# servos.net
KiCad netlist of a schematic drawn in Altium Designer
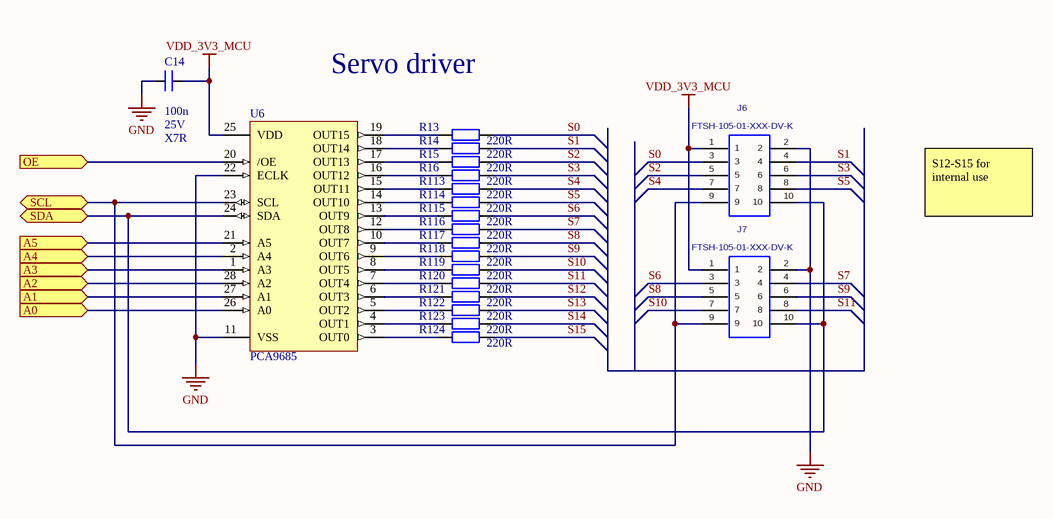
[diagram p0: servos.SchDoc]

(export (version "E")
  (design (tool "Eeschema 10.0.6"))
  (components
    (comp (ref "C14")
      (value "100n")
      (footprint "C1005[0402]")
      (description "Capacitor")
      (fields (field (name "VOLTAGE") "25V") (field (name "TYPE") "X7R") (field (name "Comment") "cap"))
      (libsource (lib "gpa_passives") (part "cap"))
    )
    (comp (ref "J6")
      (value "FTSH-105-01-XXX-DV-K")
      (footprint "FTSH-105-01-XXX-DV-K")
      (description "TERMINAL STRIP, .050\"(1.27mm) PITCH, 10 PINS, KEYED")
      (fields (field (name "MANUFACTURER") "SAMTEC") (field (name "CREATED") "November 30, 2016 - Wendy Xin"))
      (libsource (lib "FTSH-105-01-XXX-DV-K") (part "FTSH-105-01-XXX-DV-K"))
    )
    (comp (ref "J7")
      (value "FTSH-105-01-XXX-DV-K")
      (footprint "FTSH-105-01-XXX-DV-K")
      (description "TERMINAL STRIP, .050\"(1.27mm) PITCH, 10 PINS, KEYED")
      (fields (field (name "MANUFACTURER") "SAMTEC") (field (name "CREATED") "November 30, 2016 - Wendy Xin"))
      (libsource (lib "FTSH-105-01-XXX-DV-K") (part "FTSH-105-01-XXX-DV-K"))
    )
    (comp (ref "R13")
      (value "220R")
      (footprint "R1005[0402]")
      (description "Resistor")
      (fields (field (name "TOLERANCE") "5%") (field (name "Comment") "res"))
      (libsource (lib "gpa_passives") (part "res"))
    )
    (comp (ref "R14")
      (value "220R")
      (footprint "R1005[0402]")
      (description "Resistor")
      (fields (field (name "TOLERANCE") "5%") (field (name "Comment") "res"))
      (libsource (lib "gpa_passives") (part "res"))
    )
    (comp (ref "R15")
      (value "220R")
      (footprint "R1005[0402]")
      (description "Resistor")
      (fields (field (name "TOLERANCE") "5%") (field (name "Comment") "res"))
      (libsource (lib "gpa_passives") (part "res"))
    )
    (comp (ref "R16")
      (value "220R")
      (footprint "R1005[0402]")
      (description "Resistor")
      (fields (field (name "TOLERANCE") "5%") (field (name "Comment") "res"))
      (libsource (lib "gpa_passives") (part "res"))
    )
    (comp (ref "R113")
      (value "220R")
      (footprint "R1005[0402]")
      (description "Resistor")
      (fields (field (name "TOLERANCE") "5%") (field (name "Comment") "res"))
      (libsource (lib "gpa_passives") (part "res"))
    )
    (comp (ref "R114")
      (value "220R")
      (footprint "R1005[0402]")
      (description "Resistor")
      (fields (field (name "TOLERANCE") "5%") (field (name "Comment") "res"))
      (libsource (lib "gpa_passives") (part "res"))
    )
    (comp (ref "R115")
      (value "220R")
      (footprint "R1005[0402]")
      (description "Resistor")
      (fields (field (name "TOLERANCE") "5%") (field (name "Comment") "res"))
      (libsource (lib "gpa_passives") (part "res"))
    )
    (comp (ref "R116")
      (value "220R")
      (footprint "R1005[0402]")
      (description "Resistor")
      (fields (field (name "TOLERANCE") "5%") (field (name "Comment") "res"))
      (libsource (lib "gpa_passives") (part "res"))
    )
    (comp (ref "R117")
      (value "220R")
      (footprint "R1005[0402]")
      (description "Resistor")
      (fields (field (name "TOLERANCE") "5%") (field (name "Comment") "res"))
      (libsource (lib "gpa_passives") (part "res"))
    )
    (comp (ref "R118")
      (value "220R")
      (footprint "R1005[0402]")
      (description "Resistor")
      (fields (field (name "TOLERANCE") "5%") (field (name "Comment") "res"))
      (libsource (lib "gpa_passives") (part "res"))
    )
    (comp (ref "R119")
      (value "220R")
      (footprint "R1005[0402]")
      (description "Resistor")
      (fields (field (name "TOLERANCE") "5%") (field (name "Comment") "res"))
      (libsource (lib "gpa_passives") (part "res"))
    )
    (comp (ref "R120")
      (value "220R")
      (footprint "R1005[0402]")
      (description "Resistor")
      (fields (field (name "TOLERANCE") "5%") (field (name "Comment") "res"))
      (libsource (lib "gpa_passives") (part "res"))
    )
    (comp (ref "R121")
      (value "220R")
      (footprint "R1005[0402]")
      (description "Resistor")
      (fields (field (name "TOLERANCE") "5%") (field (name "Comment") "res"))
      (libsource (lib "gpa_passives") (part "res"))
    )
    (comp (ref "R122")
      (value "220R")
      (footprint "R1005[0402]")
      (description "Resistor")
      (fields (field (name "TOLERANCE") "5%") (field (name "Comment") "res"))
      (libsource (lib "gpa_passives") (part "res"))
    )
    (comp (ref "R123")
      (value "220R")
      (footprint "R1005[0402]")
      (description "Resistor")
      (fields (field (name "TOLERANCE") "5%") (field (name "Comment") "res"))
      (libsource (lib "gpa_passives") (part "res"))
    )
    (comp (ref "R124")
      (value "220R")
      (footprint "R1005[0402]")
      (description "Resistor")
      (fields (field (name "TOLERANCE") "5%") (field (name "Comment") "res"))
      (libsource (lib "gpa_passives") (part "res"))
    )
    (comp (ref "U6")
      (value "PCA9685")
      (footprint "NXP_QFN65P600X600X100_HS-29M")
      (libsource (lib "gpa_nxp") (part "pca9685"))
    )
  )
  (nets
    (net (code "1") (name "/A0") (class "Default")
      (node (ref "U6") (pin "26") (pinfunction "A0_26") (pintype "input"))
    )
    (net (code "2") (name "/A1") (class "Default")
      (node (ref "U6") (pin "27") (pinfunction "A1_27") (pintype "input"))
    )
    (net (code "3") (name "/A2") (class "Default")
      (node (ref "U6") (pin "28") (pinfunction "A2_28") (pintype "input"))
    )
    (net (code "4") (name "/A3") (class "Default")
      (node (ref "U6") (pin "1") (pinfunction "A3_1") (pintype "input"))
    )
    (net (code "5") (name "/A4") (class "Default")
      (node (ref "U6") (pin "2") (pinfunction "A4_2") (pintype "input"))
    )
    (net (code "6") (name "/A5") (class "Default")
      (node (ref "U6") (pin "21") (pinfunction "A5_21") (pintype "input"))
    )
    (net (code "7") (name "/OE") (class "Default")
      (node (ref "U6") (pin "20") (pinfunction "/OE_20") (pintype "input"))
    )
    (net (code "8") (name "/S0") (class "Default")
      (node (ref "J6") (pin "3") (pinfunction "3_3") (pintype "passive"))
      (node (ref "R13") (pin "2") (pinfunction "2_2") (pintype "passive"))
    )
    (net (code "9") (name "/S1") (class "Default")
      (node (ref "J6") (pin "4") (pinfunction "4_4") (pintype "passive"))
      (node (ref "R14") (pin "2") (pinfunction "2_2") (pintype "passive"))
    )
    (net (code "10") (name "/S2") (class "Default")
      (node (ref "J6") (pin "5") (pinfunction "5_5") (pintype "passive"))
      (node (ref "R15") (pin "2") (pinfunction "2_2") (pintype "passive"))
    )
    (net (code "11") (name "/S3") (class "Default")
      (node (ref "J6") (pin "6") (pinfunction "6_6") (pintype "passive"))
      (node (ref "R16") (pin "2") (pinfunction "2_2") (pintype "passive"))
    )
    (net (code "12") (name "/S4") (class "Default")
      (node (ref "J6") (pin "7") (pinfunction "7_7") (pintype "passive"))
      (node (ref "R113") (pin "2") (pinfunction "2_2") (pintype "passive"))
    )
    (net (code "13") (name "/S5") (class "Default")
      (node (ref "J6") (pin "8") (pinfunction "8_8") (pintype "passive"))
      (node (ref "R114") (pin "2") (pinfunction "2_2") (pintype "passive"))
    )
    (net (code "14") (name "/S6") (class "Default")
      (node (ref "J7") (pin "3") (pinfunction "3_3") (pintype "passive"))
      (node (ref "R115") (pin "2") (pinfunction "2_2") (pintype "passive"))
    )
    (net (code "15") (name "/S7") (class "Default")
      (node (ref "J7") (pin "4") (pinfunction "4_4") (pintype "passive"))
      (node (ref "R116") (pin "2") (pinfunction "2_2") (pintype "passive"))
    )
    (net (code "16") (name "/S8") (class "Default")
      (node (ref "J7") (pin "5") (pinfunction "5_5") (pintype "passive"))
      (node (ref "R117") (pin "2") (pinfunction "2_2") (pintype "passive"))
    )
    (net (code "17") (name "/S9") (class "Default")
      (node (ref "J7") (pin "6") (pinfunction "6_6") (pintype "passive"))
      (node (ref "R118") (pin "2") (pinfunction "2_2") (pintype "passive"))
    )
    (net (code "18") (name "/S10") (class "Default")
      (node (ref "J7") (pin "7") (pinfunction "7_7") (pintype "passive"))
      (node (ref "R119") (pin "2") (pinfunction "2_2") (pintype "passive"))
    )
    (net (code "19") (name "/S11") (class "Default")
      (node (ref "J7") (pin "8") (pinfunction "8_8") (pintype "passive"))
      (node (ref "R120") (pin "2") (pinfunction "2_2") (pintype "passive"))
    )
    (net (code "20") (name "/S12") (class "Default")
      (node (ref "R121") (pin "2") (pinfunction "2_2") (pintype "passive"))
    )
    (net (code "21") (name "/S13") (class "Default")
      (node (ref "R122") (pin "2") (pinfunction "2_2") (pintype "passive"))
    )
    (net (code "22") (name "/S14") (class "Default")
      (node (ref "R123") (pin "2") (pinfunction "2_2") (pintype "passive"))
    )
    (net (code "23") (name "/S15") (class "Default")
      (node (ref "R124") (pin "2") (pinfunction "2_2") (pintype "passive"))
    )
    (net (code "24") (name "/SCL") (class "Default")
      (node (ref "J6") (pin "9") (pinfunction "9_9") (pintype "passive"))
      (node (ref "J7") (pin "9") (pinfunction "9_9") (pintype "passive"))
      (node (ref "U6") (pin "23") (pinfunction "SCL_23") (pintype "bidirectional"))
    )
    (net (code "25") (name "/SDA") (class "Default")
      (node (ref "J6") (pin "10") (pinfunction "10_10") (pintype "passive"))
      (node (ref "J7") (pin "10") (pinfunction "10_10") (pintype "passive"))
      (node (ref "U6") (pin "24") (pinfunction "SDA_24") (pintype "bidirectional"))
    )
    (net (code "26") (name "GND") (class "Default")
      (node (ref "C14") (pin "1") (pinfunction "1_1") (pintype "passive"))
      (node (ref "J6") (pin "2") (pinfunction "2_2") (pintype "passive"))
      (node (ref "J7") (pin "2") (pinfunction "2_2") (pintype "passive"))
      (node (ref "U6") (pin "11") (pinfunction "VSS_11") (pintype "power_in"))
      (node (ref "U6") (pin "22") (pinfunction "ECLK_22") (pintype "input"))
    )
    (net (code "27") (name "Net-(U6-OUT0)") (class "Default")
      (node (ref "R124") (pin "1") (pinfunction "1_1") (pintype "passive"))
      (node (ref "U6") (pin "3") (pinfunction "OUT0_3") (pintype "output"))
    )
    (net (code "28") (name "Net-(U6-OUT1)") (class "Default")
      (node (ref "R123") (pin "1") (pinfunction "1_1") (pintype "passive"))
      (node (ref "U6") (pin "4") (pinfunction "OUT1_4") (pintype "output"))
    )
    (net (code "29") (name "Net-(U6-OUT2)") (class "Default")
      (node (ref "R122") (pin "1") (pinfunction "1_1") (pintype "passive"))
      (node (ref "U6") (pin "5") (pinfunction "OUT2_5") (pintype "output"))
    )
    (net (code "30") (name "Net-(U6-OUT3)") (class "Default")
      (node (ref "R121") (pin "1") (pinfunction "1_1") (pintype "passive"))
      (node (ref "U6") (pin "6") (pinfunction "OUT3_6") (pintype "output"))
    )
    (net (code "31") (name "Net-(U6-OUT4)") (class "Default")
      (node (ref "R120") (pin "1") (pinfunction "1_1") (pintype "passive"))
      (node (ref "U6") (pin "7") (pinfunction "OUT4_7") (pintype "output"))
    )
    (net (code "32") (name "Net-(U6-OUT5)") (class "Default")
      (node (ref "R119") (pin "1") (pinfunction "1_1") (pintype "passive"))
      (node (ref "U6") (pin "8") (pinfunction "OUT5_8") (pintype "output"))
    )
    (net (code "33") (name "Net-(U6-OUT6)") (class "Default")
      (node (ref "R118") (pin "1") (pinfunction "1_1") (pintype "passive"))
      (node (ref "U6") (pin "9") (pinfunction "OUT6_9") (pintype "output"))
    )
    (net (code "34") (name "Net-(U6-OUT7)") (class "Default")
      (node (ref "R117") (pin "1") (pinfunction "1_1") (pintype "passive"))
      (node (ref "U6") (pin "10") (pinfunction "OUT7_10") (pintype "output"))
    )
    (net (code "35") (name "Net-(U6-OUT8)") (class "Default")
      (node (ref "R116") (pin "1") (pinfunction "1_1") (pintype "passive"))
      (node (ref "U6") (pin "12") (pinfunction "OUT8_12") (pintype "output"))
    )
    (net (code "36") (name "Net-(U6-OUT9)") (class "Default")
      (node (ref "R115") (pin "1") (pinfunction "1_1") (pintype "passive"))
      (node (ref "U6") (pin "13") (pinfunction "OUT9_13") (pintype "output"))
    )
    (net (code "37") (name "Net-(U6-OUT10)") (class "Default")
      (node (ref "R114") (pin "1") (pinfunction "1_1") (pintype "passive"))
      (node (ref "U6") (pin "14") (pinfunction "OUT10_14") (pintype "output"))
    )
    (net (code "38") (name "Net-(U6-OUT11)") (class "Default")
      (node (ref "R113") (pin "1") (pinfunction "1_1") (pintype "passive"))
      (node (ref "U6") (pin "15") (pinfunction "OUT11_15") (pintype "output"))
    )
    (net (code "39") (name "Net-(U6-OUT12)") (class "Default")
      (node (ref "R16") (pin "1") (pinfunction "1_1") (pintype "passive"))
      (node (ref "U6") (pin "16") (pinfunction "OUT12_16") (pintype "output"))
    )
    (net (code "40") (name "Net-(U6-OUT13)") (class "Default")
      (node (ref "R15") (pin "1") (pinfunction "1_1") (pintype "passive"))
      (node (ref "U6") (pin "17") (pinfunction "OUT13_17") (pintype "output"))
    )
    (net (code "41") (name "Net-(U6-OUT14)") (class "Default")
      (node (ref "R14") (pin "1") (pinfunction "1_1") (pintype "passive"))
      (node (ref "U6") (pin "18") (pinfunction "OUT14_18") (pintype "output"))
    )
    (net (code "42") (name "Net-(U6-OUT15)") (class "Default")
      (node (ref "R13") (pin "1") (pinfunction "1_1") (pintype "passive"))
      (node (ref "U6") (pin "19") (pinfunction "OUT15_19") (pintype "output"))
    )
    (net (code "43") (name "VDD_3V3_MCU") (class "Default")
      (node (ref "C14") (pin "2") (pinfunction "2_2") (pintype "passive"))
      (node (ref "J6") (pin "1") (pinfunction "1_1") (pintype "passive"))
      (node (ref "J7") (pin "1") (pinfunction "1_1") (pintype "passive"))
      (node (ref "U6") (pin "25") (pinfunction "VDD_25") (pintype "power_in"))
    )
  )
)
